# CPU-WiFi.net
KiCad netlist of a schematic drawn in Altium Designer
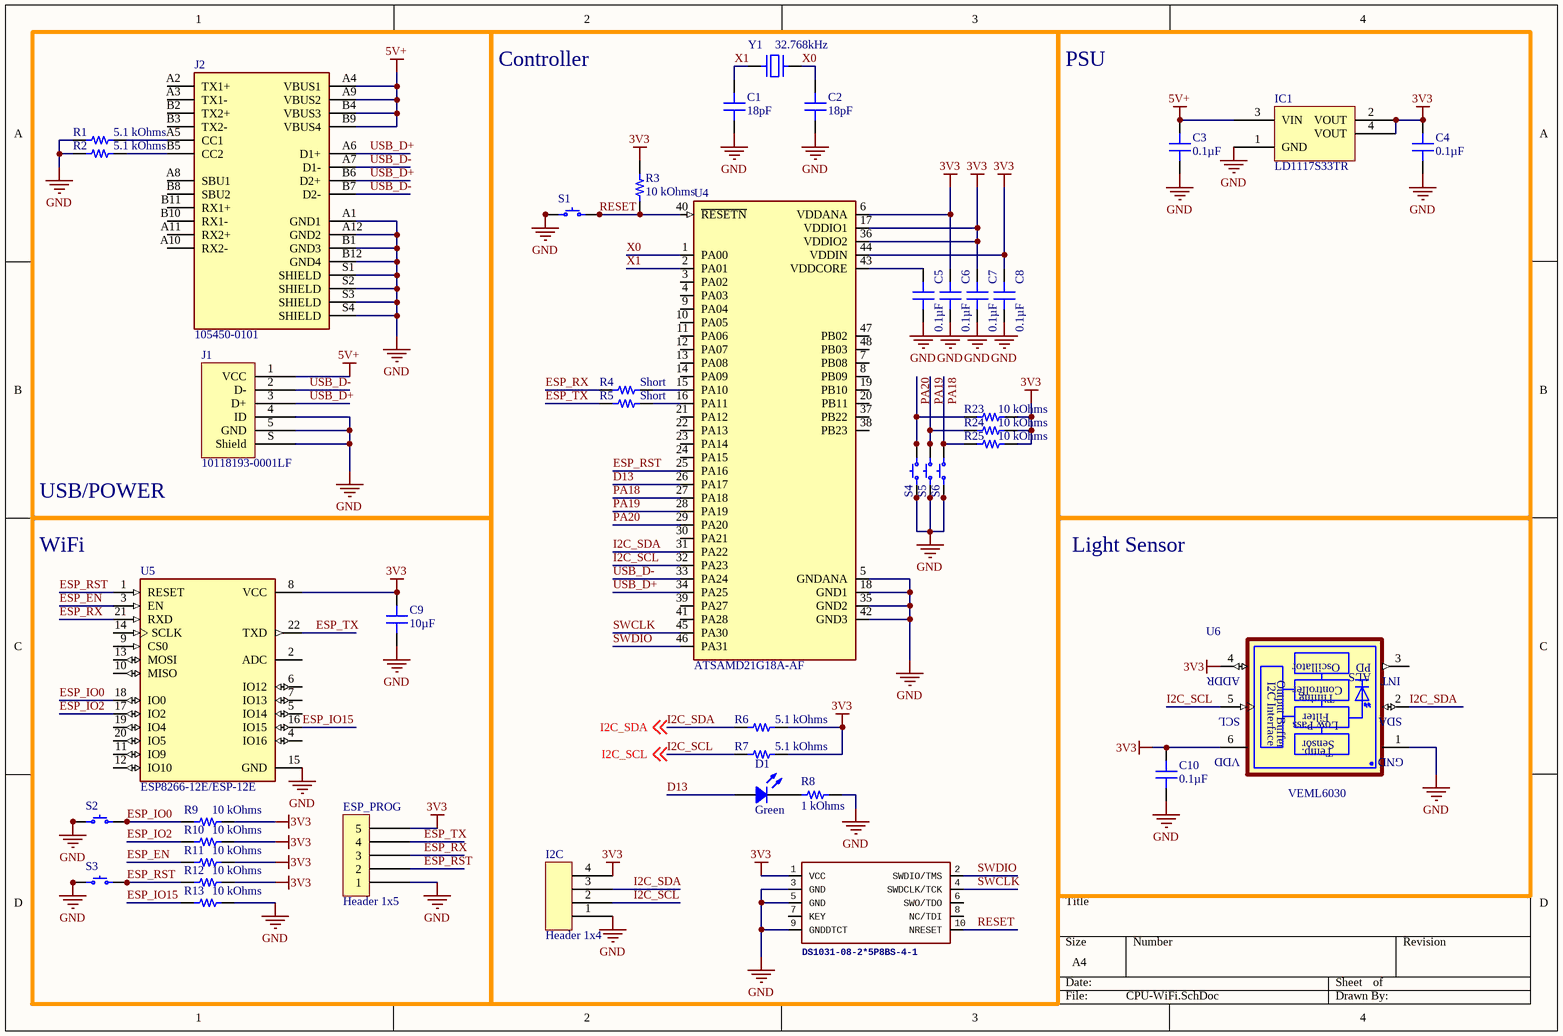
[diagram p0: CPU-WiFi.SchDoc]

(export (version "E")
  (design (tool "Eeschema 10.0.6"))
  (components
    (comp (ref "C1")
      (value "18pF")
      (footprint "CAP 0603_1608")
      (description "CAP CER 18PF 50V C0G/NP0 0603")
      (fields (field (name "PART NUMBER") "C0603X180J5GACTU") (field (name "MANUFACTURER") "KEMET"))
      (libsource (lib "Altium Master") (part "Capacitor"))
    )
    (comp (ref "C2")
      (value "18pF")
      (footprint "CAP 0603_1608")
      (description "CAP CER 18PF 50V C0G/NP0 0603")
      (fields (field (name "PART NUMBER") "C0603X180J5GACTU") (field (name "MANUFACTURER") "KEMET"))
      (libsource (lib "Altium Master") (part "Capacitor"))
    )
    (comp (ref "C3")
      (value "0.1µF")
      (footprint "CAP 0603_1608")
      (description "CAP CER 0.1UF 25V X7R 0603")
      (fields (field (name "PART NUMBER") "C0603T104K3RAL7867") (field (name "MANUFACTURER") "KEMET"))
      (libsource (lib "Altium Master") (part "Capacitor"))
    )
    (comp (ref "C4")
      (value "0.1µF")
      (footprint "CAP 0603_1608")
      (description "CAP CER 0.1UF 25V X7R 0603")
      (fields (field (name "PART NUMBER") "C0603T104K3RAL7867") (field (name "MANUFACTURER") "KEMET"))
      (libsource (lib "Altium Master") (part "Capacitor"))
    )
    (comp (ref "C5")
      (value "0.1µF")
      (footprint "CAP 0603_1608")
      (description "CAP CER 0.1UF 25V X7R 0603")
      (fields (field (name "PART NUMBER") "C0603T104K3RAL7867") (field (name "MANUFACTURER") "KEMET"))
      (libsource (lib "Altium Master") (part "Capacitor"))
    )
    (comp (ref "C6")
      (value "0.1µF")
      (footprint "CAP 0603_1608")
      (description "CAP CER 0.1UF 25V X7R 0603")
      (fields (field (name "PART NUMBER") "C0603T104K3RAL7867") (field (name "MANUFACTURER") "KEMET"))
      (libsource (lib "Altium Master") (part "Capacitor"))
    )
    (comp (ref "C7")
      (value "0.1µF")
      (footprint "CAP 0603_1608")
      (description "CAP CER 0.1UF 25V X7R 0603")
      (fields (field (name "PART NUMBER") "C0603T104K3RAL7867") (field (name "MANUFACTURER") "KEMET"))
      (libsource (lib "Altium Master") (part "Capacitor"))
    )
    (comp (ref "C8")
      (value "0.1µF")
      (footprint "CAP 0603_1608")
      (description "CAP CER 0.1UF 25V X7R 0603")
      (fields (field (name "PART NUMBER") "C0603T104K3RAL7867") (field (name "MANUFACTURER") "KEMET"))
      (libsource (lib "Altium Master") (part "Capacitor"))
    )
    (comp (ref "C9")
      (value "10µF")
      (footprint "CAP 0603_1608")
      (description "CAP CER 10UF 6.3V X5R 0603")
      (fields
        (field (name "PART NUMBER") "GRM188R60J106ME47D")
        (field (name "MANUFACTURER") "Murata Electronics")
      )
      (libsource (lib "Altium Master") (part "Capacitor"))
    )
    (comp (ref "C10")
      (value "0.1µF")
      (footprint "CAP 0603_1608")
      (description "CAP CER 0.1UF 25V X7R 0603")
      (fields (field (name "PART NUMBER") "C0603T104K3RAL7867") (field (name "MANUFACTURER") "KEMET"))
      (libsource (lib "Altium Master") (part "Capacitor"))
    )
    (comp (ref "D1")
      (value "Green")
      (footprint "LED 0805_2012 GREEN")
      (description "LED GREEN CLEAR SMD")
      (fields
        (field (name "PART NUMBER") "SML-LX0805UPGC-TR")
        (field (name "MANUFACTURER") "Lumex Opto/Components Inc.")
      )
      (libsource (lib "Altium Master") (part "LED"))
    )
    (comp (ref "ESP_PROG")
      (value "Header 1x5")
      (footprint "Header 1x5 male")
      (libsource (lib "Lib") (part "Header 1x5"))
    )
    (comp (ref "I2C")
      (value "Header 1x4")
      (footprint "Header 1x4 male")
      (libsource (lib "Lib") (part "Header 1x4"))
    )
    (comp (ref "IC1")
      (value "LD1117S33TR")
      (footprint "ST SOT-223")
      (description "IC REG LINEAR 3.3V 800MA SOT223")
      (fields (field (name "MANUFACTURER") "STMicroelectronics"))
      (libsource (lib "Altium Master") (part "ST LD1117"))
    )
    (comp (ref "J1")
      (value "10118193-0001LF")
      (footprint "FCI USB 10118193-0001LF")
      (description "CONN RCPT USB2.0 MICRO B SMD R/A")
      (fields (field (name "MANUFACTURER") "Amphenol ICC (FCI)"))
      (libsource (lib "Altium Master") (part "USB 2.0 Type B Micro"))
    )
    (comp (ref "J2")
      (value "105450-0101")
      (footprint "SnapEDApcb:MOLEX_105450-0101")
      (fields
        (field (name "MF") "Molex")
        (field (name "DIGI-KEY_PART_NUMBER") "WM12856CT-ND")
        (field (name "MP") "1054500101")
      )
      (libsource (lib "105450-0101") (part "105450-0101"))
    )
    (comp (ref "PROG1")
      (value "DS1031-08-2*5P8BS-4-1")
      (footprint "2X5-PTH-1.27MM")
      (description "Cortex Debug ConnectorDatasheet")
      (libsource (lib "samd21") (part "CORTEX_DEBUGPTH"))
    )
    (comp (ref "R1")
      (value "5.1 kOhms")
      (footprint "RES 0603_1608")
      (description "RES SMD 5.1K OHM 5% 1/10W 0603")
      (fields (field (name "PART NUMBER") "AC0603JR-075K1L") (field (name "MANUFACTURER") "Yageo"))
      (libsource (lib "Altium Master") (part "Resistor"))
    )
    (comp (ref "R2")
      (value "5.1 kOhms")
      (footprint "RES 0603_1608")
      (description "RES SMD 5.1K OHM 5% 1/10W 0603")
      (fields (field (name "PART NUMBER") "AC0603JR-075K1L") (field (name "MANUFACTURER") "Yageo"))
      (libsource (lib "Altium Master") (part "Resistor"))
    )
    (comp (ref "R3")
      (value "10 kOhms")
      (footprint "RES 0603_1608")
      (description "RES SMD 10K OHM 0.1% 1/16W 0603")
      (fields
        (field (name "PART NUMBER") "CPF0603B10KE")
        (field (name "MANUFACTURER") "TE Connectivity Passive Product")
      )
      (libsource (lib "Altium Master") (part "Resistor"))
    )
    (comp (ref "R4")
      (value "Short")
      (footprint "RES 0603_1608")
      (description "RES 0 OHM JUMPER 1/4W 0603")
      (fields
        (field (name "PART NUMBER") "HCJ0603ZT0R00")
        (field (name "MANUFACTURER") "Stackpole Electronics Inc")
      )
      (libsource (lib "Altium Master") (part "Resistor"))
    )
    (comp (ref "R5")
      (value "Short")
      (footprint "RES 0603_1608")
      (description "RES 0 OHM JUMPER 1/4W 0603")
      (fields
        (field (name "PART NUMBER") "HCJ0603ZT0R00")
        (field (name "MANUFACTURER") "Stackpole Electronics Inc")
      )
      (libsource (lib "Altium Master") (part "Resistor"))
    )
    (comp (ref "R6")
      (value "5.1 kOhms")
      (footprint "RES 0603_1608")
      (description "RES SMD 5.1K OHM 5% 1/10W 0603")
      (fields (field (name "PART NUMBER") "AC0603JR-075K1L") (field (name "MANUFACTURER") "Yageo"))
      (libsource (lib "Altium Master") (part "Resistor"))
    )
    (comp (ref "R7")
      (value "5.1 kOhms")
      (footprint "RES 0603_1608")
      (description "RES SMD 5.1K OHM 5% 1/10W 0603")
      (fields (field (name "PART NUMBER") "AC0603JR-075K1L") (field (name "MANUFACTURER") "Yageo"))
      (libsource (lib "Altium Master") (part "Resistor"))
    )
    (comp (ref "R8")
      (value "1 kOhms")
      (footprint "RES 0603_1608")
      (description "RES SMD 1K OHM 1% 1/10W 0603")
      (fields (field (name "PART NUMBER") "CR0603-FX-1001ELF") (field (name "MANUFACTURER") "Bourns Inc."))
      (libsource (lib "Altium Master") (part "Resistor"))
    )
    (comp (ref "R9")
      (value "10 kOhms")
      (footprint "RES 0603_1608")
      (description "RES SMD 10K OHM 0.1% 1/16W 0603")
      (fields
        (field (name "PART NUMBER") "CPF0603B10KE")
        (field (name "MANUFACTURER") "TE Connectivity Passive Product")
      )
      (libsource (lib "Altium Master") (part "Resistor"))
    )
    (comp (ref "R10")
      (value "10 kOhms")
      (footprint "RES 0603_1608")
      (description "RES SMD 10K OHM 0.1% 1/16W 0603")
      (fields
        (field (name "PART NUMBER") "CPF0603B10KE")
        (field (name "MANUFACTURER") "TE Connectivity Passive Product")
      )
      (libsource (lib "Altium Master") (part "Resistor"))
    )
    (comp (ref "R11")
      (value "10 kOhms")
      (footprint "RES 0603_1608")
      (description "RES SMD 10K OHM 0.1% 1/16W 0603")
      (fields
        (field (name "PART NUMBER") "CPF0603B10KE")
        (field (name "MANUFACTURER") "TE Connectivity Passive Product")
      )
      (libsource (lib "Altium Master") (part "Resistor"))
    )
    (comp (ref "R12")
      (value "10 kOhms")
      (footprint "RES 0603_1608")
      (description "RES SMD 10K OHM 0.1% 1/16W 0603")
      (fields
        (field (name "PART NUMBER") "CPF0603B10KE")
        (field (name "MANUFACTURER") "TE Connectivity Passive Product")
      )
      (libsource (lib "Altium Master") (part "Resistor"))
    )
    (comp (ref "R13")
      (value "10 kOhms")
      (footprint "RES 0603_1608")
      (description "RES SMD 10K OHM 0.1% 1/16W 0603")
      (fields
        (field (name "PART NUMBER") "CPF0603B10KE")
        (field (name "MANUFACTURER") "TE Connectivity Passive Product")
      )
      (libsource (lib "Altium Master") (part "Resistor"))
    )
    (comp (ref "R23")
      (value "10 kOhms")
      (footprint "RES 0603_1608")
      (description "RES SMD 10K OHM 0.1% 1/16W 0603")
      (fields
        (field (name "PART NUMBER") "CPF0603B10KE")
        (field (name "MANUFACTURER") "TE Connectivity Passive Product")
      )
      (libsource (lib "Altium Master") (part "Resistor"))
    )
    (comp (ref "R24")
      (value "10 kOhms")
      (footprint "RES 0603_1608")
      (description "RES SMD 10K OHM 0.1% 1/16W 0603")
      (fields
        (field (name "PART NUMBER") "CPF0603B10KE")
        (field (name "MANUFACTURER") "TE Connectivity Passive Product")
      )
      (libsource (lib "Altium Master") (part "Resistor"))
    )
    (comp (ref "R25")
      (value "10 kOhms")
      (footprint "RES 0603_1608")
      (description "RES SMD 10K OHM 0.1% 1/16W 0603")
      (fields
        (field (name "PART NUMBER") "CPF0603B10KE")
        (field (name "MANUFACTURER") "TE Connectivity Passive Product")
      )
      (libsource (lib "Altium Master") (part "Resistor"))
    )
    (comp (ref "S1")
      (value "B3S-1000P")
      (footprint "OMRON B3S-1000P")
      (description "SWITCH TACTILE SPST-NO 0.05A 24V")
      (fields (field (name "MANUFACTURER") "Omron Electronics Inc-EMC Div"))
      (libsource (lib "Altium Master") (part "SPST-NO 4 PIN"))
    )
    (comp (ref "S2")
      (value "B3S-1000P")
      (footprint "OMRON B3S-1000P")
      (description "SWITCH TACTILE SPST-NO 0.05A 24V")
      (fields (field (name "MANUFACTURER") "Omron Electronics Inc-EMC Div"))
      (libsource (lib "Altium Master") (part "SPST-NO 4 PIN"))
    )
    (comp (ref "S3")
      (value "B3S-1000P")
      (footprint "OMRON B3S-1000P")
      (description "SWITCH TACTILE SPST-NO 0.05A 24V")
      (fields (field (name "MANUFACTURER") "Omron Electronics Inc-EMC Div"))
      (libsource (lib "Altium Master") (part "SPST-NO 4 PIN"))
    )
    (comp (ref "S4")
      (value "B3S-1000P")
      (footprint "OMRON B3S-1000P")
      (description "SWITCH TACTILE SPST-NO 0.05A 24V")
      (fields (field (name "MANUFACTURER") "Omron Electronics Inc-EMC Div"))
      (libsource (lib "Altium Master") (part "SPST-NO 4 PIN"))
    )
    (comp (ref "S5")
      (value "B3S-1000P")
      (footprint "OMRON B3S-1000P")
      (description "SWITCH TACTILE SPST-NO 0.05A 24V")
      (fields (field (name "MANUFACTURER") "Omron Electronics Inc-EMC Div"))
      (libsource (lib "Altium Master") (part "SPST-NO 4 PIN"))
    )
    (comp (ref "S6")
      (value "B3S-1000P")
      (footprint "OMRON B3S-1000P")
      (description "SWITCH TACTILE SPST-NO 0.05A 24V")
      (fields (field (name "MANUFACTURER") "Omron Electronics Inc-EMC Div"))
      (libsource (lib "Altium Master") (part "SPST-NO 4 PIN"))
    )
    (comp (ref "U4")
      (value "ATSAMD21G18A-AF")
      (footprint "QFP50P900X900X120-48N")
      (fields (field (name "MF") "Microchip"))
      (libsource (lib "ATSAMD21G18A-AF") (part "ATSAMD21G18A-AF"))
    )
    (comp (ref "U5")
      (value "ESP8266-12E/ESP-12E")
      (footprint "XCVR_ESP8266-12E/ESP-12E")
      (fields (field (name "MF") "AI-Thinker"))
      (libsource (lib "ESP8266-12E_ESP-12E") (part "ESP8266-12E/ESP-12E"))
    )
    (comp (ref "U6")
      (value "VEML6030")
      (footprint "VISHAY_VEML6030_2X2X0.87")
      (description "Optical Sensor Ambient 550nm IÂ²C 6-SMD, No Lead")
      (fields (field (name "MF") "Vishay"))
      (libsource (lib "VEML6030") (part "VEML6030"))
    )
    (comp (ref "Y1")
      (value "32.768kHz")
      (footprint "ABRACON ABS07")
      (description "CRYSTAL 32.7680KHZ 12.5PF SMD")
      (fields (field (name "PART NUMBER") "ABS07-32.768KHZ-T") (field (name "MANUFACTURER") "Abracon LLC"))
      (libsource (lib "Altium Master") (part "Abracon Crystal ABS07"))
    )
  )
  (nets
    (net (code "1") (name "/D13") (class "Default")
      (node (ref "D1") (pin "1") (pinfunction "1_1") (pintype "passive"))
      (node (ref "U4") (pin "26") (pinfunction "PA17_26") (pintype "bidirectional"))
    )
    (net (code "2") (name "/ESP_EN") (class "Default")
      (node (ref "R11") (pin "1") (pinfunction "1_1") (pintype "passive"))
      (node (ref "U5") (pin "3") (pinfunction "EN_3") (pintype "input"))
    )
    (net (code "3") (name "/ESP_IO0") (class "Default")
      (node (ref "R9") (pin "1") (pinfunction "1_1") (pintype "passive"))
      (node (ref "S2") (pin "3") (pinfunction "3_3") (pintype "passive"))
      (node (ref "S2") (pin "4") (pinfunction "4_4") (pintype "passive"))
      (node (ref "U5") (pin "18") (pinfunction "IO0_18") (pintype "bidirectional"))
    )
    (net (code "4") (name "/ESP_IO2") (class "Default")
      (node (ref "R10") (pin "1") (pinfunction "1_1") (pintype "passive"))
      (node (ref "U5") (pin "17") (pinfunction "IO2_17") (pintype "bidirectional"))
    )
    (net (code "5") (name "/ESP_IO15") (class "Default")
      (node (ref "R13") (pin "1") (pinfunction "1_1") (pintype "passive"))
      (node (ref "U5") (pin "16") (pinfunction "IO15_16") (pintype "bidirectional"))
    )
    (net (code "6") (name "/ESP_RST") (class "Default")
      (node (ref "ESP_PROG") (pin "2") (pinfunction "2_2") (pintype "passive"))
      (node (ref "R12") (pin "1") (pinfunction "1_1") (pintype "passive"))
      (node (ref "S3") (pin "3") (pinfunction "3_3") (pintype "passive"))
      (node (ref "S3") (pin "4") (pinfunction "4_4") (pintype "passive"))
      (node (ref "U4") (pin "25") (pinfunction "PA16_25") (pintype "bidirectional"))
      (node (ref "U5") (pin "1") (pinfunction "RESET_1") (pintype "input"))
    )
    (net (code "7") (name "/ESP_RX") (class "Default")
      (node (ref "ESP_PROG") (pin "3") (pinfunction "3_3") (pintype "passive"))
      (node (ref "R4") (pin "1") (pinfunction "1_1") (pintype "passive"))
      (node (ref "U5") (pin "21") (pinfunction "RXD_21") (pintype "input"))
    )
    (net (code "8") (name "/ESP_TX") (class "Default")
      (node (ref "ESP_PROG") (pin "4") (pinfunction "4_4") (pintype "passive"))
      (node (ref "R5") (pin "1") (pinfunction "1_1") (pintype "passive"))
      (node (ref "U5") (pin "22") (pinfunction "TXD_22") (pintype "output"))
    )
    (net (code "9") (name "/PA18") (class "Default")
      (node (ref "R25") (pin "2") (pinfunction "2_2") (pintype "passive"))
      (node (ref "S6") (pin "3") (pinfunction "3_3") (pintype "passive"))
      (node (ref "S6") (pin "4") (pinfunction "4_4") (pintype "passive"))
      (node (ref "U4") (pin "27") (pinfunction "PA18_27") (pintype "bidirectional"))
    )
    (net (code "10") (name "/PA19") (class "Default")
      (node (ref "R24") (pin "2") (pinfunction "2_2") (pintype "passive"))
      (node (ref "S5") (pin "3") (pinfunction "3_3") (pintype "passive"))
      (node (ref "S5") (pin "4") (pinfunction "4_4") (pintype "passive"))
      (node (ref "U4") (pin "28") (pinfunction "PA19_28") (pintype "bidirectional"))
    )
    (net (code "11") (name "/PA20") (class "Default")
      (node (ref "R23") (pin "2") (pinfunction "2_2") (pintype "passive"))
      (node (ref "S4") (pin "3") (pinfunction "3_3") (pintype "passive"))
      (node (ref "S4") (pin "4") (pinfunction "4_4") (pintype "passive"))
      (node (ref "U4") (pin "29") (pinfunction "PA20_29") (pintype "bidirectional"))
    )
    (net (code "12") (name "/RESET") (class "Default")
      (node (ref "PROG1") (pin "10") (pinfunction "NRESET_10") (pintype "passive"))
      (node (ref "R3") (pin "1") (pinfunction "1_1") (pintype "passive"))
      (node (ref "S1") (pin "3") (pinfunction "3_3") (pintype "passive"))
      (node (ref "S1") (pin "4") (pinfunction "4_4") (pintype "passive"))
      (node (ref "U4") (pin "40") (pinfunction "~{RESETN}_40") (pintype "input"))
    )
    (net (code "13") (name "/SWCLK") (class "Default")
      (node (ref "PROG1") (pin "4") (pinfunction "SWDCLK/TCK_4") (pintype "passive"))
      (node (ref "U4") (pin "45") (pinfunction "PA30_45") (pintype "bidirectional"))
    )
    (net (code "14") (name "/SWDIO") (class "Default")
      (node (ref "PROG1") (pin "2") (pinfunction "SWDIO/TMS_2") (pintype "passive"))
      (node (ref "U4") (pin "46") (pinfunction "PA31_46") (pintype "bidirectional"))
    )
    (net (code "15") (name "/USB_D+") (class "Default")
      (node (ref "J1") (pin "3") (pinfunction "D+_3") (pintype "passive"))
      (node (ref "J2") (pin "A6") (pinfunction "D1+_A6") (pintype "passive"))
      (node (ref "J2") (pin "B6") (pinfunction "D2+_B6") (pintype "passive"))
      (node (ref "U4") (pin "34") (pinfunction "PA25_34") (pintype "bidirectional"))
    )
    (net (code "16") (name "/USB_D-") (class "Default")
      (node (ref "J1") (pin "2") (pinfunction "D-_2") (pintype "passive"))
      (node (ref "J2") (pin "A7") (pinfunction "D1-_A7") (pintype "passive"))
      (node (ref "J2") (pin "B7") (pinfunction "D2-_B7") (pintype "passive"))
      (node (ref "U4") (pin "33") (pinfunction "PA24_33") (pintype "bidirectional"))
    )
    (net (code "17") (name "/X0") (class "Default")
      (node (ref "C2") (pin "2") (pinfunction "2_2") (pintype "passive"))
      (node (ref "U4") (pin "1") (pinfunction "PA00_1") (pintype "bidirectional"))
      (node (ref "Y1") (pin "2") (pinfunction "2_2") (pintype "passive"))
    )
    (net (code "18") (name "/X1") (class "Default")
      (node (ref "C1") (pin "2") (pinfunction "2_2") (pintype "passive"))
      (node (ref "U4") (pin "2") (pinfunction "PA01_2") (pintype "bidirectional"))
      (node (ref "Y1") (pin "1") (pinfunction "1_1") (pintype "passive"))
    )
    (net (code "19") (name "3V3") (class "Default")
      (node (ref "C10") (pin "2") (pinfunction "2_2") (pintype "passive"))
      (node (ref "C4") (pin "2") (pinfunction "2_2") (pintype "passive"))
      (node (ref "C6") (pin "2") (pinfunction "2_2") (pintype "passive"))
      (node (ref "C7") (pin "2") (pinfunction "2_2") (pintype "passive"))
      (node (ref "C8") (pin "2") (pinfunction "2_2") (pintype "passive"))
      (node (ref "C9") (pin "2") (pinfunction "2_2") (pintype "passive"))
      (node (ref "ESP_PROG") (pin "5") (pinfunction "5_5") (pintype "passive"))
      (node (ref "I2C") (pin "4") (pinfunction "4_4") (pintype "passive"))
      (node (ref "IC1") (pin "2") (pinfunction "VOUT_2") (pintype "passive"))
      (node (ref "IC1") (pin "4") (pinfunction "VOUT_4") (pintype "passive"))
      (node (ref "PROG1") (pin "1") (pinfunction "VCC_1") (pintype "passive"))
      (node (ref "R10") (pin "2") (pinfunction "2_2") (pintype "passive"))
      (node (ref "R11") (pin "2") (pinfunction "2_2") (pintype "passive"))
      (node (ref "R12") (pin "2") (pinfunction "2_2") (pintype "passive"))
      (node (ref "R23") (pin "1") (pinfunction "1_1") (pintype "passive"))
      (node (ref "R24") (pin "1") (pinfunction "1_1") (pintype "passive"))
      (node (ref "R25") (pin "1") (pinfunction "1_1") (pintype "passive"))
      (node (ref "R3") (pin "2") (pinfunction "2_2") (pintype "passive"))
      (node (ref "R6") (pin "2") (pinfunction "2_2") (pintype "passive"))
      (node (ref "R7") (pin "2") (pinfunction "2_2") (pintype "passive"))
      (node (ref "R9") (pin "2") (pinfunction "2_2") (pintype "passive"))
      (node (ref "U4") (pin "17") (pinfunction "VDDIO1_17") (pintype "power_in"))
      (node (ref "U4") (pin "36") (pinfunction "VDDIO2_36") (pintype "power_in"))
      (node (ref "U4") (pin "44") (pinfunction "VDDIN_44") (pintype "power_in"))
      (node (ref "U4") (pin "6") (pinfunction "VDDANA_6") (pintype "power_in"))
      (node (ref "U5") (pin "8") (pinfunction "VCC_8") (pintype "power_in"))
      (node (ref "U6") (pin "4") (pinfunction "ADDR_4") (pintype "bidirectional"))
      (node (ref "U6") (pin "6") (pinfunction "VDD_6") (pintype "power_in"))
    )
    (net (code "20") (name "5V+") (class "Default")
      (node (ref "C3") (pin "2") (pinfunction "2_2") (pintype "passive"))
      (node (ref "IC1") (pin "3") (pinfunction "VIN_3") (pintype "passive"))
      (node (ref "J1") (pin "1") (pinfunction "VCC_1") (pintype "passive"))
      (node (ref "J2") (pin "A4") (pinfunction "VBUS1_A4") (pintype "passive"))
      (node (ref "J2") (pin "A9") (pinfunction "VBUS2_A9") (pintype "passive"))
      (node (ref "J2") (pin "B4") (pinfunction "VBUS3_B4") (pintype "passive"))
      (node (ref "J2") (pin "B9") (pinfunction "VBUS4_B9") (pintype "passive"))
    )
    (net (code "21") (name "GND") (class "Default")
      (node (ref "C1") (pin "1") (pinfunction "1_1") (pintype "passive"))
      (node (ref "C10") (pin "1") (pinfunction "1_1") (pintype "passive"))
      (node (ref "C2") (pin "1") (pinfunction "1_1") (pintype "passive"))
      (node (ref "C3") (pin "1") (pinfunction "1_1") (pintype "passive"))
      (node (ref "C4") (pin "1") (pinfunction "1_1") (pintype "passive"))
      (node (ref "C5") (pin "1") (pinfunction "1_1") (pintype "passive"))
      (node (ref "C6") (pin "1") (pinfunction "1_1") (pintype "passive"))
      (node (ref "C7") (pin "1") (pinfunction "1_1") (pintype "passive"))
      (node (ref "C8") (pin "1") (pinfunction "1_1") (pintype "passive"))
      (node (ref "C9") (pin "1") (pinfunction "1_1") (pintype "passive"))
      (node (ref "ESP_PROG") (pin "1") (pinfunction "1_1") (pintype "passive"))
      (node (ref "I2C") (pin "1") (pinfunction "1_1") (pintype "passive"))
      (node (ref "IC1") (pin "1") (pinfunction "GND_1") (pintype "passive"))
      (node (ref "J1") (pin "4") (pinfunction "ID_4") (pintype "passive"))
      (node (ref "J1") (pin "5") (pinfunction "GND_5") (pintype "passive"))
      (node (ref "J1") (pin "S") (pinfunction "Shield_S") (pintype "passive"))
      (node (ref "J2") (pin "A1") (pinfunction "GND1_A1") (pintype "passive"))
      (node (ref "J2") (pin "A12") (pinfunction "GND2_A12") (pintype "passive"))
      (node (ref "J2") (pin "B1") (pinfunction "GND3_B1") (pintype "passive"))
      (node (ref "J2") (pin "B12") (pinfunction "GND4_B12") (pintype "passive"))
      (node (ref "J2") (pin "S1") (pinfunction "SHIELD_S1") (pintype "passive"))
      (node (ref "J2") (pin "S2") (pinfunction "SHIELD_S2") (pintype "passive"))
      (node (ref "J2") (pin "S3") (pinfunction "SHIELD_S3") (pintype "passive"))
      (node (ref "J2") (pin "S4") (pinfunction "SHIELD_S4") (pintype "passive"))
      (node (ref "PROG1") (pin "3") (pinfunction "GND_3") (pintype "passive"))
      (node (ref "PROG1") (pin "5") (pinfunction "GND_5") (pintype "passive"))
      (node (ref "PROG1") (pin "9") (pinfunction "GNDDTCT_9") (pintype "passive"))
      (node (ref "R1") (pin "1") (pinfunction "1_1") (pintype "passive"))
      (node (ref "R13") (pin "2") (pinfunction "2_2") (pintype "passive"))
      (node (ref "R2") (pin "1") (pinfunction "1_1") (pintype "passive"))
      (node (ref "R8") (pin "2") (pinfunction "2_2") (pintype "passive"))
      (node (ref "S1") (pin "1") (pinfunction "1_1") (pintype "passive"))
      (node (ref "S1") (pin "2") (pinfunction "2_2") (pintype "passive"))
      (node (ref "S2") (pin "1") (pinfunction "1_1") (pintype "passive"))
      (node (ref "S2") (pin "2") (pinfunction "2_2") (pintype "passive"))
      (node (ref "S3") (pin "1") (pinfunction "1_1") (pintype "passive"))
      (node (ref "S3") (pin "2") (pinfunction "2_2") (pintype "passive"))
      (node (ref "S4") (pin "1") (pinfunction "1_1") (pintype "passive"))
      (node (ref "S4") (pin "2") (pinfunction "2_2") (pintype "passive"))
      (node (ref "S5") (pin "1") (pinfunction "1_1") (pintype "passive"))
      (node (ref "S5") (pin "2") (pinfunction "2_2") (pintype "passive"))
      (node (ref "S6") (pin "1") (pinfunction "1_1") (pintype "passive"))
      (node (ref "S6") (pin "2") (pinfunction "2_2") (pintype "passive"))
      (node (ref "U4") (pin "18") (pinfunction "GND1_18") (pintype "power_in"))
      (node (ref "U4") (pin "35") (pinfunction "GND2_35") (pintype "power_in"))
      (node (ref "U4") (pin "42") (pinfunction "GND3_42") (pintype "power_in"))
      (node (ref "U4") (pin "5") (pinfunction "GNDANA_5") (pintype "power_in"))
      (node (ref "U5") (pin "15") (pinfunction "GND_15") (pintype "power_in"))
      (node (ref "U6") (pin "1") (pinfunction "GND_1") (pintype "power_in"))
    )
    (net (code "22") (name "I2C_SCL") (class "Default")
      (node (ref "I2C") (pin "2") (pinfunction "2_2") (pintype "passive"))
      (node (ref "R7") (pin "1") (pinfunction "1_1") (pintype "passive"))
      (node (ref "U4") (pin "32") (pinfunction "PA23_32") (pintype "bidirectional"))
      (node (ref "U6") (pin "5") (pinfunction "SCL_5") (pintype "input"))
    )
    (net (code "23") (name "I2C_SDA") (class "Default")
      (node (ref "I2C") (pin "3") (pinfunction "3_3") (pintype "passive"))
      (node (ref "R6") (pin "1") (pinfunction "1_1") (pintype "passive"))
      (node (ref "U4") (pin "31") (pinfunction "PA22_31") (pintype "bidirectional"))
      (node (ref "U6") (pin "2") (pinfunction "SDA_2") (pintype "bidirectional"))
    )
    (net (code "24") (name "Net-(D1-Pad2)") (class "Default")
      (node (ref "D1") (pin "2") (pinfunction "2_2") (pintype "passive"))
      (node (ref "R8") (pin "1") (pinfunction "1_1") (pintype "passive"))
    )
    (net (code "25") (name "Net-(J2-CC1)") (class "Default")
      (node (ref "J2") (pin "A5") (pinfunction "CC1_A5") (pintype "passive"))
      (node (ref "R1") (pin "2") (pinfunction "2_2") (pintype "passive"))
    )
    (net (code "26") (name "Net-(J2-CC2)") (class "Default")
      (node (ref "J2") (pin "B5") (pinfunction "CC2_B5") (pintype "passive"))
      (node (ref "R2") (pin "2") (pinfunction "2_2") (pintype "passive"))
    )
    (net (code "27") (name "Net-(U4-PA10)") (class "Default")
      (node (ref "R4") (pin "2") (pinfunction "2_2") (pintype "passive"))
      (node (ref "U4") (pin "15") (pinfunction "PA10_15") (pintype "bidirectional"))
    )
    (net (code "28") (name "Net-(U4-PA11)") (class "Default")
      (node (ref "R5") (pin "2") (pinfunction "2_2") (pintype "passive"))
      (node (ref "U4") (pin "16") (pinfunction "PA11_16") (pintype "bidirectional"))
    )
    (net (code "29") (name "Net-(U4-VDDCORE)") (class "Default")
      (node (ref "C5") (pin "2") (pinfunction "2_2") (pintype "passive"))
      (node (ref "U4") (pin "43") (pinfunction "VDDCORE_43") (pintype "power_in"))
    )
    (net (code "30") (name "unconnected-(J2-RX1+-PadB11)") (class "Default")
      (node (ref "J2") (pin "B11") (pinfunction "RX1+_B11") (pintype "passive"))
    )
    (net (code "31") (name "unconnected-(J2-RX1--PadB10)") (class "Default")
      (node (ref "J2") (pin "B10") (pinfunction "RX1-_B10") (pintype "passive"))
    )
    (net (code "32") (name "unconnected-(J2-RX2+-PadA11)") (class "Default")
      (node (ref "J2") (pin "A11") (pinfunction "RX2+_A11") (pintype "passive"))
    )
    (net (code "33") (name "unconnected-(J2-RX2--PadA10)") (class "Default")
      (node (ref "J2") (pin "A10") (pinfunction "RX2-_A10") (pintype "passive"))
    )
    (net (code "34") (name "unconnected-(J2-SBU1-PadA8)") (class "Default")
      (node (ref "J2") (pin "A8") (pinfunction "SBU1_A8") (pintype "passive"))
    )
    (net (code "35") (name "unconnected-(J2-SBU2-PadB8)") (class "Default")
      (node (ref "J2") (pin "B8") (pinfunction "SBU2_B8") (pintype "passive"))
    )
    (net (code "36") (name "unconnected-(J2-TX1+-PadA2)") (class "Default")
      (node (ref "J2") (pin "A2") (pinfunction "TX1+_A2") (pintype "passive"))
    )
    (net (code "37") (name "unconnected-(J2-TX1--PadA3)") (class "Default")
      (node (ref "J2") (pin "A3") (pinfunction "TX1-_A3") (pintype "passive"))
    )
    (net (code "38") (name "unconnected-(J2-TX2+-PadB2)") (class "Default")
      (node (ref "J2") (pin "B2") (pinfunction "TX2+_B2") (pintype "passive"))
    )
    (net (code "39") (name "unconnected-(J2-TX2--PadB3)") (class "Default")
      (node (ref "J2") (pin "B3") (pinfunction "TX2-_B3") (pintype "passive"))
    )
    (net (code "40") (name "unconnected-(PROG1-KEY-Pad7)") (class "Default")
      (node (ref "PROG1") (pin "7") (pinfunction "KEY_7") (pintype "passive"))
    )
    (net (code "41") (name "unconnected-(PROG1-NC{slash}TDI-Pad8)") (class "Default")
      (node (ref "PROG1") (pin "8") (pinfunction "NC/TDI_8") (pintype "passive"))
    )
    (net (code "42") (name "unconnected-(PROG1-SWO{slash}TDO-Pad6)") (class "Default")
      (node (ref "PROG1") (pin "6") (pinfunction "SWO/TDO_6") (pintype "passive"))
    )
    (net (code "43") (name "unconnected-(U4-PA02-Pad3)") (class "Default")
      (node (ref "U4") (pin "3") (pinfunction "PA02_3") (pintype "bidirectional"))
    )
    (net (code "44") (name "unconnected-(U4-PA03-Pad4)") (class "Default")
      (node (ref "U4") (pin "4") (pinfunction "PA03_4") (pintype "bidirectional"))
    )
    (net (code "45") (name "unconnected-(U4-PA04-Pad9)") (class "Default")
      (node (ref "U4") (pin "9") (pinfunction "PA04_9") (pintype "bidirectional"))
    )
    (net (code "46") (name "unconnected-(U4-PA05-Pad10)") (class "Default")
      (node (ref "U4") (pin "10") (pinfunction "PA05_10") (pintype "bidirectional"))
    )
    (net (code "47") (name "unconnected-(U4-PA06-Pad11)") (class "Default")
      (node (ref "U4") (pin "11") (pinfunction "PA06_11") (pintype "bidirectional"))
    )
    (net (code "48") (name "unconnected-(U4-PA07-Pad12)") (class "Default")
      (node (ref "U4") (pin "12") (pinfunction "PA07_12") (pintype "bidirectional"))
    )
    (net (code "49") (name "unconnected-(U4-PA08-Pad13)") (class "Default")
      (node (ref "U4") (pin "13") (pinfunction "PA08_13") (pintype "bidirectional"))
    )
    (net (code "50") (name "unconnected-(U4-PA09-Pad14)") (class "Default")
      (node (ref "U4") (pin "14") (pinfunction "PA09_14") (pintype "bidirectional"))
    )
    (net (code "51") (name "unconnected-(U4-PA12-Pad21)") (class "Default")
      (node (ref "U4") (pin "21") (pinfunction "PA12_21") (pintype "bidirectional"))
    )
    (net (code "52") (name "unconnected-(U4-PA13-Pad22)") (class "Default")
      (node (ref "U4") (pin "22") (pinfunction "PA13_22") (pintype "bidirectional"))
    )
    (net (code "53") (name "unconnected-(U4-PA14-Pad23)") (class "Default")
      (node (ref "U4") (pin "23") (pinfunction "PA14_23") (pintype "bidirectional"))
    )
    (net (code "54") (name "unconnected-(U4-PA15-Pad24)") (class "Default")
      (node (ref "U4") (pin "24") (pinfunction "PA15_24") (pintype "bidirectional"))
    )
    (net (code "55") (name "unconnected-(U4-PA21-Pad30)") (class "Default")
      (node (ref "U4") (pin "30") (pinfunction "PA21_30") (pintype "bidirectional"))
    )
    (net (code "56") (name "unconnected-(U4-PA27-Pad39)") (class "Default")
      (node (ref "U4") (pin "39") (pinfunction "PA27_39") (pintype "bidirectional"))
    )
    (net (code "57") (name "unconnected-(U4-PA28-Pad41)") (class "Default")
      (node (ref "U4") (pin "41") (pinfunction "PA28_41") (pintype "bidirectional"))
    )
    (net (code "58") (name "unconnected-(U4-PB02-Pad47)") (class "Default")
      (node (ref "U4") (pin "47") (pinfunction "PB02_47") (pintype "bidirectional"))
    )
    (net (code "59") (name "unconnected-(U4-PB03-Pad48)") (class "Default")
      (node (ref "U4") (pin "48") (pinfunction "PB03_48") (pintype "bidirectional"))
    )
    (net (code "60") (name "unconnected-(U4-PB08-Pad7)") (class "Default")
      (node (ref "U4") (pin "7") (pinfunction "PB08_7") (pintype "bidirectional"))
    )
    (net (code "61") (name "unconnected-(U4-PB09-Pad8)") (class "Default")
      (node (ref "U4") (pin "8") (pinfunction "PB09_8") (pintype "bidirectional"))
    )
    (net (code "62") (name "unconnected-(U4-PB10-Pad19)") (class "Default")
      (node (ref "U4") (pin "19") (pinfunction "PB10_19") (pintype "bidirectional"))
    )
    (net (code "63") (name "unconnected-(U4-PB11-Pad20)") (class "Default")
      (node (ref "U4") (pin "20") (pinfunction "PB11_20") (pintype "bidirectional"))
    )
    (net (code "64") (name "unconnected-(U4-PB22-Pad37)") (class "Default")
      (node (ref "U4") (pin "37") (pinfunction "PB22_37") (pintype "bidirectional"))
    )
    (net (code "65") (name "unconnected-(U4-PB23-Pad38)") (class "Default")
      (node (ref "U4") (pin "38") (pinfunction "PB23_38") (pintype "bidirectional"))
    )
    (net (code "66") (name "unconnected-(U5-ADC-Pad2)") (class "Default")
      (node (ref "U5") (pin "2") (pinfunction "ADC_2") (pintype "passive"))
    )
    (net (code "67") (name "unconnected-(U5-CS0-Pad9)") (class "Default")
      (node (ref "U5") (pin "9") (pinfunction "CS0_9") (pintype "input"))
    )
    (net (code "68") (name "unconnected-(U5-IO4-Pad19)") (class "Default")
      (node (ref "U5") (pin "19") (pinfunction "IO4_19") (pintype "bidirectional"))
    )
    (net (code "69") (name "unconnected-(U5-IO5-Pad20)") (class "Default")
      (node (ref "U5") (pin "20") (pinfunction "IO5_20") (pintype "bidirectional"))
    )
    (net (code "70") (name "unconnected-(U5-IO9-Pad11)") (class "Default")
      (node (ref "U5") (pin "11") (pinfunction "IO9_11") (pintype "bidirectional"))
    )
    (net (code "71") (name "unconnected-(U5-IO10-Pad12)") (class "Default")
      (node (ref "U5") (pin "12") (pinfunction "IO10_12") (pintype "bidirectional"))
    )
    (net (code "72") (name "unconnected-(U5-IO12-Pad6)") (class "Default")
      (node (ref "U5") (pin "6") (pinfunction "IO12_6") (pintype "bidirectional"))
    )
    (net (code "73") (name "unconnected-(U5-IO13-Pad7)") (class "Default")
      (node (ref "U5") (pin "7") (pinfunction "IO13_7") (pintype "bidirectional"))
    )
    (net (code "74") (name "unconnected-(U5-IO14-Pad5)") (class "Default")
      (node (ref "U5") (pin "5") (pinfunction "IO14_5") (pintype "bidirectional"))
    )
    (net (code "75") (name "unconnected-(U5-IO16-Pad4)") (class "Default")
      (node (ref "U5") (pin "4") (pinfunction "IO16_4") (pintype "bidirectional"))
    )
    (net (code "76") (name "unconnected-(U5-MISO-Pad10)") (class "Default")
      (node (ref "U5") (pin "10") (pinfunction "MISO_10") (pintype "bidirectional"))
    )
    (net (code "77") (name "unconnected-(U5-MOSI-Pad13)") (class "Default")
      (node (ref "U5") (pin "13") (pinfunction "MOSI_13") (pintype "bidirectional"))
    )
    (net (code "78") (name "unconnected-(U5-SCLK-Pad14)") (class "Default")
      (node (ref "U5") (pin "14") (pinfunction "SCLK_14") (pintype "input"))
    )
    (net (code "79") (name "unconnected-(U6-INT-Pad3)") (class "Default")
      (node (ref "U6") (pin "3") (pinfunction "INT_3") (pintype "output"))
    )
  )
)
